# Dribbler.net
KiCad netlist of a schematic drawn in EAGLE
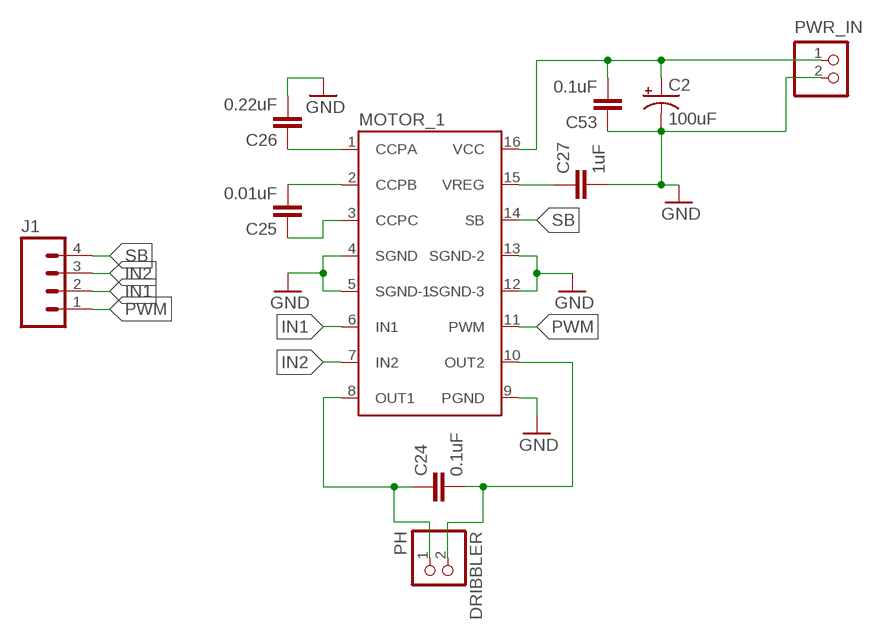
[diagram p0: schematic, sheet 2]

(export (version "E")
  (design (tool "Eeschema 10.0.6"))
  (components
    (comp (ref "C2")
      (value "100uF")
      (footprint "eagle-import:CPOL-RADIAL-100UF-25V")
      (libsource (lib "eagle-import") (part "CAP_POLPTH1"))
    )
    (comp (ref "C24")
      (value "0.1uF")
      (footprint "eagle-import:0603-CAP")
      (libsource (lib "eagle-import") (part "CAP0603-CAP"))
    )
    (comp (ref "C25")
      (value "0.01uF")
      (footprint "eagle-import:0603-CAP")
      (libsource (lib "eagle-import") (part "CAP0603-CAP"))
    )
    (comp (ref "C26")
      (value "0.22uF")
      (footprint "eagle-import:0603-CAP")
      (libsource (lib "eagle-import") (part "CAP0603-CAP"))
    )
    (comp (ref "C27")
      (value "1uF")
      (footprint "eagle-import:0603-CAP")
      (libsource (lib "eagle-import") (part "CAP0603-CAP"))
    )
    (comp (ref "C53")
      (value "0.1uF")
      (footprint "eagle-import:0603-CAP")
      (libsource (lib "eagle-import") (part "CAP0603-CAP"))
    )
    (comp (ref "DRIBBLER")
      (value "PH")
      (footprint "eagle-import:JST-PH-2-THM")
      (libsource (lib "eagle-import") (part "JST_2PIN-THM"))
    )
    (comp (ref "J1")
      (value "M04PTH")
      (footprint "eagle-import:1X04")
      (libsource (lib "eagle-import") (part "M04PTH"))
    )
    (comp (ref "MOTOR_1")
      (value "TB6549PG")
      (footprint "eagle-import:TB6549PG")
      (libsource (lib "eagle-import") (part "TB6549PG"))
    )
    (comp (ref "PWR_IN")
      (value "B2P-VH")
      (footprint "eagle-import:B2P-VH")
      (libsource (lib "eagle-import") (part "B2P-VH"))
    )
  )
  (nets
    (net (code "1") (name "GND") (class "Default")
      (node (ref "C2") (pin "2") (pinfunction "-_2") (pintype "passive"))
      (node (ref "C26") (pin "2") (pinfunction "2_2") (pintype "passive"))
      (node (ref "C27") (pin "2") (pinfunction "2_2") (pintype "passive"))
      (node (ref "C53") (pin "1") (pinfunction "1_1") (pintype "passive"))
      (node (ref "MOTOR_1") (pin "12") (pinfunction "SGND-3_12") (pintype "bidirectional"))
      (node (ref "MOTOR_1") (pin "13") (pinfunction "SGND-2_13") (pintype "bidirectional"))
      (node (ref "MOTOR_1") (pin "4") (pinfunction "SGND_4") (pintype "bidirectional"))
      (node (ref "MOTOR_1") (pin "5") (pinfunction "SGND-1_5") (pintype "bidirectional"))
      (node (ref "MOTOR_1") (pin "9") (pinfunction "PGND_9") (pintype "bidirectional"))
      (node (ref "PWR_IN") (pin "2") (pinfunction "2_2") (pintype "passive"))
    )
    (net (code "2") (name "IN1") (class "Default")
      (node (ref "J1") (pin "2") (pinfunction "2_2") (pintype "passive"))
      (node (ref "MOTOR_1") (pin "6") (pinfunction "IN1_6") (pintype "bidirectional"))
    )
    (net (code "3") (name "IN2") (class "Default")
      (node (ref "J1") (pin "3") (pinfunction "3_3") (pintype "passive"))
      (node (ref "MOTOR_1") (pin "7") (pinfunction "IN2_7") (pintype "bidirectional"))
    )
    (net (code "4") (name "Net-(C2-+)") (class "Default")
      (node (ref "C2") (pin "1") (pinfunction "+_1") (pintype "passive"))
      (node (ref "C53") (pin "2") (pinfunction "2_2") (pintype "passive"))
      (node (ref "MOTOR_1") (pin "16") (pinfunction "VCC_16") (pintype "bidirectional"))
      (node (ref "PWR_IN") (pin "1") (pinfunction "1_1") (pintype "passive"))
    )
    (net (code "5") (name "Net-(DRIBBLER-1)") (class "Default")
      (node (ref "C24") (pin "2") (pinfunction "2_2") (pintype "passive"))
      (node (ref "DRIBBLER") (pin "2") (pinfunction "1_2") (pintype "passive"))
      (node (ref "MOTOR_1") (pin "10") (pinfunction "OUT2_10") (pintype "bidirectional"))
    )
    (net (code "6") (name "Net-(DRIBBLER-2)") (class "Default")
      (node (ref "C24") (pin "1") (pinfunction "1_1") (pintype "passive"))
      (node (ref "DRIBBLER") (pin "1") (pinfunction "2_1") (pintype "passive"))
      (node (ref "MOTOR_1") (pin "8") (pinfunction "OUT1_8") (pintype "bidirectional"))
    )
    (net (code "7") (name "Net-(MOTOR_1-CCPA)") (class "Default")
      (node (ref "C26") (pin "1") (pinfunction "1_1") (pintype "passive"))
      (node (ref "MOTOR_1") (pin "1") (pinfunction "CCPA_1") (pintype "bidirectional"))
    )
    (net (code "8") (name "Net-(MOTOR_1-CCPB)") (class "Default")
      (node (ref "C25") (pin "2") (pinfunction "2_2") (pintype "passive"))
      (node (ref "MOTOR_1") (pin "2") (pinfunction "CCPB_2") (pintype "bidirectional"))
    )
    (net (code "9") (name "Net-(MOTOR_1-CCPC)") (class "Default")
      (node (ref "C25") (pin "1") (pinfunction "1_1") (pintype "passive"))
      (node (ref "MOTOR_1") (pin "3") (pinfunction "CCPC_3") (pintype "bidirectional"))
    )
    (net (code "10") (name "Net-(MOTOR_1-VREG)") (class "Default")
      (node (ref "C27") (pin "1") (pinfunction "1_1") (pintype "passive"))
      (node (ref "MOTOR_1") (pin "15") (pinfunction "VREG_15") (pintype "bidirectional"))
    )
    (net (code "11") (name "PWM") (class "Default")
      (node (ref "J1") (pin "1") (pinfunction "1_1") (pintype "passive"))
      (node (ref "MOTOR_1") (pin "11") (pinfunction "PWM_11") (pintype "bidirectional"))
    )
    (net (code "12") (name "SB") (class "Default")
      (node (ref "J1") (pin "4") (pinfunction "4_4") (pintype "passive"))
      (node (ref "MOTOR_1") (pin "14") (pinfunction "SB_14") (pintype "bidirectional"))
    )
  )
)
